# bee_duel_played.net
KiCad netlist of a schematic drawn in EAGLE
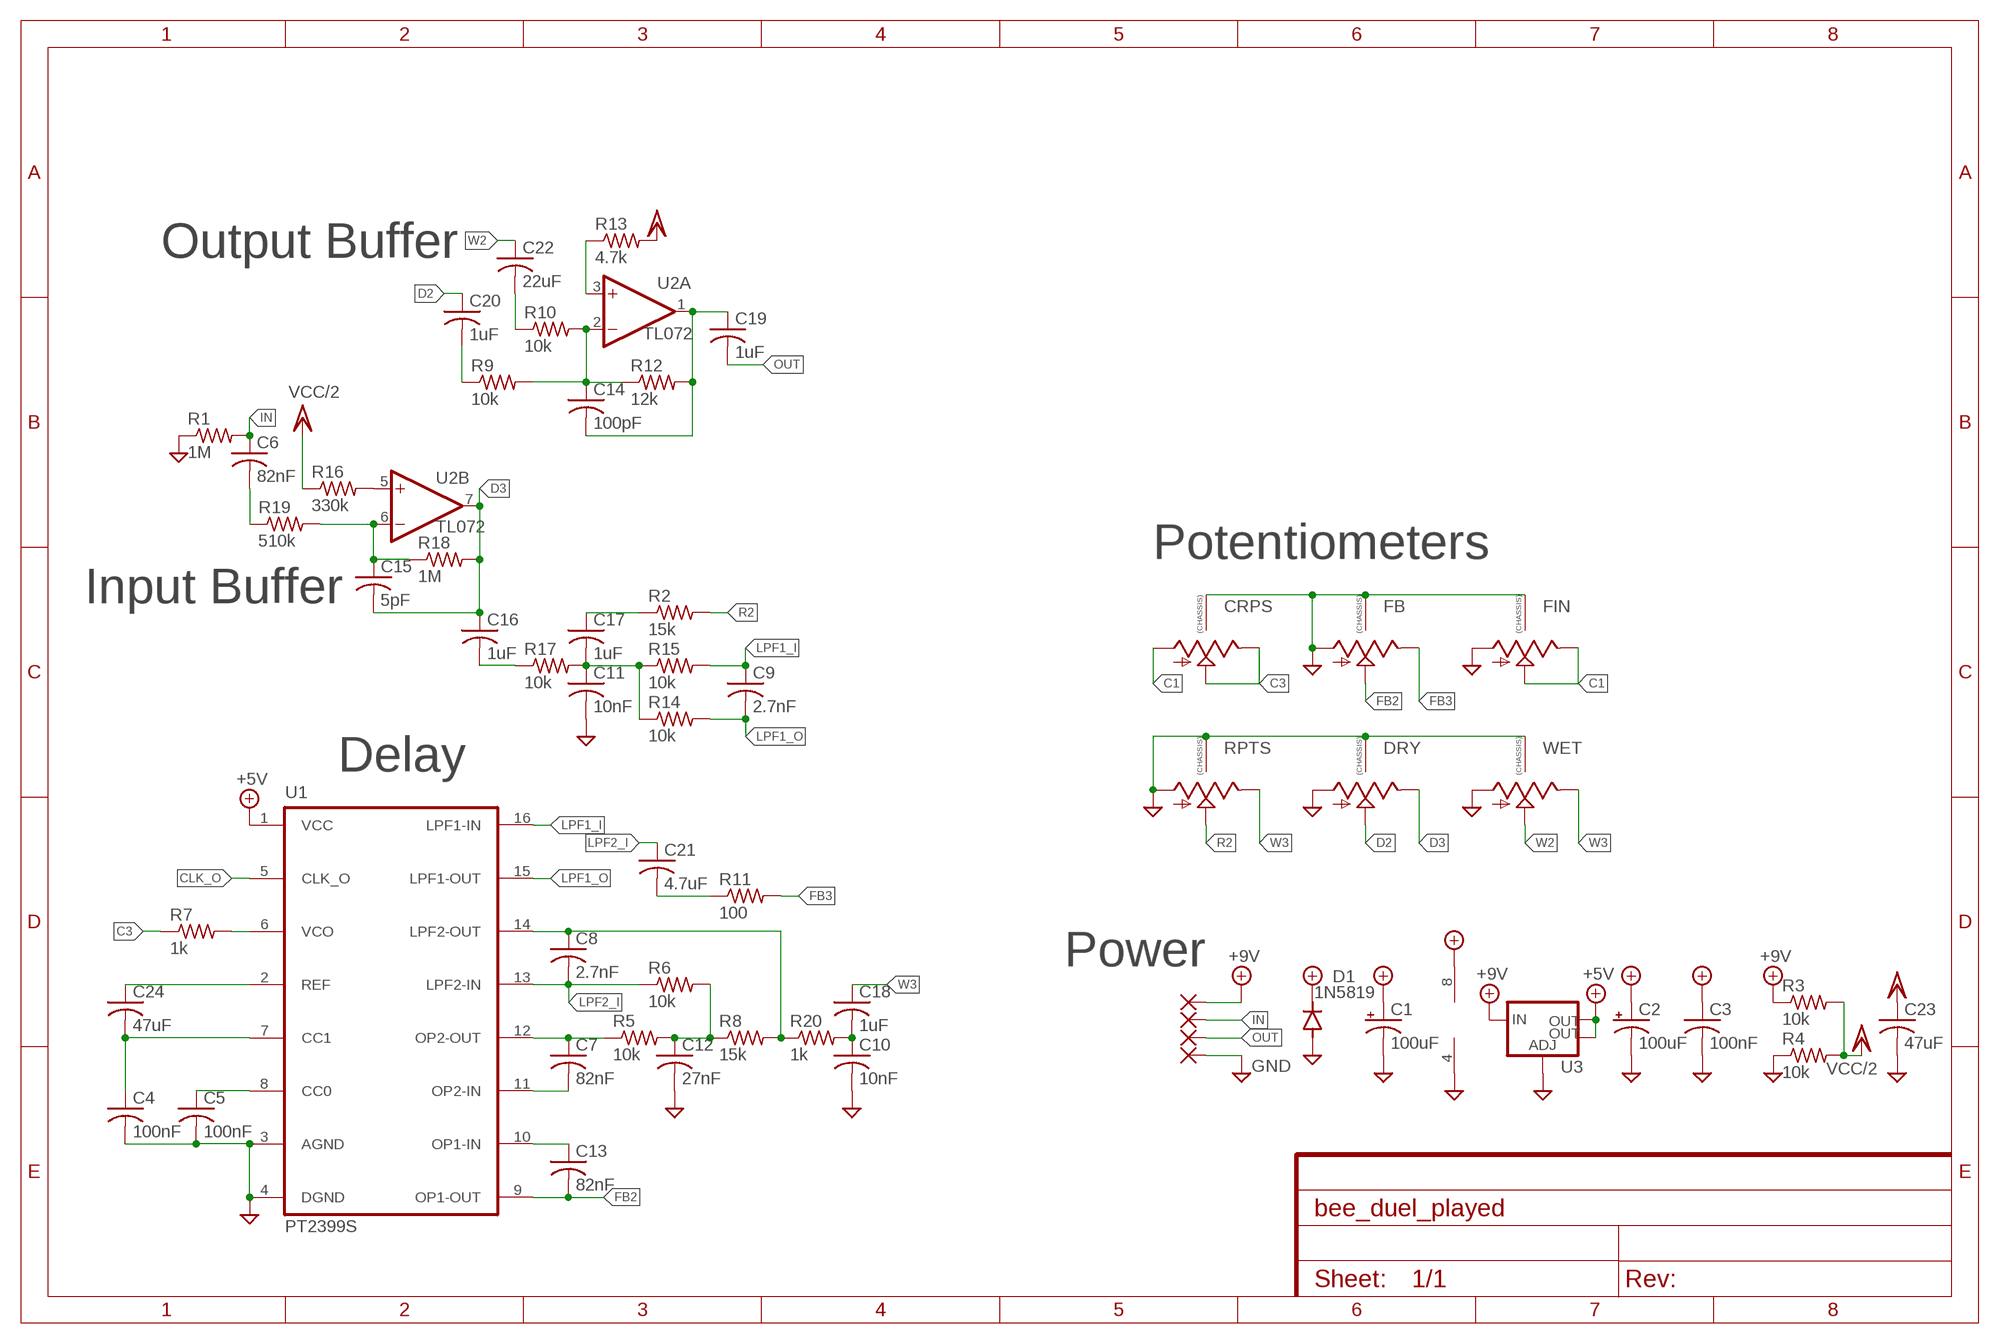
[diagram p0: schematic, sheet 1]

(export (version "E")
  (design (tool "Eeschema 10.0.6"))
  (components
    (comp (ref "C1")
      (value "100uF")
      (footprint "eagle-import:CPOL-RADIAL-2.5MM-6.5MM")
      (libsource (lib "eagle-import") (part "100UF-POLAR-RADIAL-2.5MM-25V-20%"))
    )
    (comp (ref "C2")
      (value "100uF")
      (footprint "eagle-import:CPOL-RADIAL-2.5MM-6.5MM")
      (libsource (lib "eagle-import") (part "100UF-POLAR-RADIAL-2.5MM-25V-20%"))
    )
    (comp (ref "C3")
      (value "100nF")
      (footprint "eagle-import:C0603")
      (libsource (lib "eagle-import") (part "C-USC0603"))
    )
    (comp (ref "C4")
      (value "100nF")
      (footprint "eagle-import:C0603")
      (libsource (lib "eagle-import") (part "C-USC0603"))
    )
    (comp (ref "C5")
      (value "100nF")
      (footprint "eagle-import:C0603")
      (libsource (lib "eagle-import") (part "C-USC0603"))
    )
    (comp (ref "C6")
      (value "82nF")
      (footprint "eagle-import:C0603")
      (libsource (lib "eagle-import") (part "C-USC0603"))
    )
    (comp (ref "C7")
      (value "82nF")
      (footprint "eagle-import:C0603")
      (libsource (lib "eagle-import") (part "C-USC0603"))
    )
    (comp (ref "C8")
      (value "2.7nF")
      (footprint "eagle-import:C0603")
      (libsource (lib "eagle-import") (part "C-USC0603"))
    )
    (comp (ref "C9")
      (value "2.7nF")
      (footprint "eagle-import:C0603")
      (libsource (lib "eagle-import") (part "C-USC0603"))
    )
    (comp (ref "C10")
      (value "10nF")
      (footprint "eagle-import:C0603")
      (libsource (lib "eagle-import") (part "C-USC0603"))
    )
    (comp (ref "C11")
      (value "10nF")
      (footprint "eagle-import:C0603")
      (libsource (lib "eagle-import") (part "C-USC0603"))
    )
    (comp (ref "C12")
      (value "27nF")
      (footprint "eagle-import:C0603")
      (libsource (lib "eagle-import") (part "C-USC0603"))
    )
    (comp (ref "C13")
      (value "82nF")
      (footprint "eagle-import:C0603")
      (libsource (lib "eagle-import") (part "C-USC0603"))
    )
    (comp (ref "C14")
      (value "100pF")
      (footprint "eagle-import:C0603")
      (libsource (lib "eagle-import") (part "C-USC0603"))
    )
    (comp (ref "C15")
      (value "5pF")
      (footprint "eagle-import:C0603")
      (libsource (lib "eagle-import") (part "C-USC0603"))
    )
    (comp (ref "C16")
      (value "1uF")
      (footprint "eagle-import:C0603")
      (libsource (lib "eagle-import") (part "C-USC0603"))
    )
    (comp (ref "C17")
      (value "1uF")
      (footprint "eagle-import:C0603")
      (libsource (lib "eagle-import") (part "C-USC0603"))
    )
    (comp (ref "C18")
      (value "1uF")
      (footprint "eagle-import:C0603")
      (libsource (lib "eagle-import") (part "C-USC0603"))
    )
    (comp (ref "C19")
      (value "1uF")
      (footprint "eagle-import:C0603")
      (libsource (lib "eagle-import") (part "C-USC0603"))
    )
    (comp (ref "C20")
      (value "1uF")
      (footprint "eagle-import:C0603")
      (libsource (lib "eagle-import") (part "C-USC0603"))
    )
    (comp (ref "C21")
      (value "4.7uF")
      (footprint "eagle-import:C0805")
      (libsource (lib "eagle-import") (part "C-USC0805"))
    )
    (comp (ref "C22")
      (value "22uF")
      (footprint "eagle-import:C1210")
      (libsource (lib "eagle-import") (part "adafruit_420_C-USC1210"))
    )
    (comp (ref "C23")
      (value "47uF")
      (footprint "eagle-import:C1210")
      (libsource (lib "eagle-import") (part "adafruit_420_C-USC1210"))
    )
    (comp (ref "C24")
      (value "47uF")
      (footprint "eagle-import:C1210")
      (libsource (lib "eagle-import") (part "adafruit_420_C-USC1210"))
    )
    (comp (ref "CRPS")
      (value "9MM_SNAP-IN_POT_CHASSIS")
      (footprint "eagle-import:9MM_SNAP-IN_POT")
      (libsource (lib "eagle-import") (part "9MM_SNAP-IN_POT_CHASSIS"))
    )
    (comp (ref "D1")
      (value "1N5819")
      (footprint "eagle-import:SOD123")
      (libsource (lib "eagle-import") (part "DIODE-SOD123"))
    )
    (comp (ref "DRY")
      (value "9MM_SNAP-IN_POT_CHASSIS")
      (footprint "eagle-import:9MM_SNAP-IN_POT")
      (libsource (lib "eagle-import") (part "9MM_SNAP-IN_POT_CHASSIS"))
    )
    (comp (ref "FB")
      (value "9MM_SNAP-IN_POT_CHASSIS")
      (footprint "eagle-import:9MM_SNAP-IN_POT")
      (libsource (lib "eagle-import") (part "9MM_SNAP-IN_POT_CHASSIS"))
    )
    (comp (ref "FIN")
      (value "9MM_SNAP-IN_POT_CHASSIS")
      (footprint "eagle-import:9MM_SNAP-IN_POT")
      (libsource (lib "eagle-import") (part "9MM_SNAP-IN_POT_CHASSIS"))
    )
    (comp (ref "PAD1")
      (value "1,6/0,8")
      (footprint "eagle-import:1,6_0,8")
      (libsource (lib "eagle-import") (part "1,6/0,8"))
    )
    (comp (ref "PAD2")
      (value "1,6/0,8")
      (footprint "eagle-import:1,6_0,8")
      (libsource (lib "eagle-import") (part "1,6/0,8"))
    )
    (comp (ref "PAD3")
      (value "1,6/0,8")
      (footprint "eagle-import:1,6_0,8")
      (libsource (lib "eagle-import") (part "1,6/0,8"))
    )
    (comp (ref "PAD4")
      (value "1,6/0,8")
      (footprint "eagle-import:1,6_0,8")
      (libsource (lib "eagle-import") (part "1,6/0,8"))
    )
    (comp (ref "R1")
      (value "1M")
      (footprint "eagle-import:R0603")
      (libsource (lib "eagle-import") (part "R-US_R0603"))
    )
    (comp (ref "R2")
      (value "15k")
      (footprint "eagle-import:R0603")
      (libsource (lib "eagle-import") (part "R-US_R0603"))
    )
    (comp (ref "R3")
      (value "10k")
      (footprint "eagle-import:R0603")
      (libsource (lib "eagle-import") (part "R-US_R0603"))
    )
    (comp (ref "R4")
      (value "10k")
      (footprint "eagle-import:R0603")
      (libsource (lib "eagle-import") (part "R-US_R0603"))
    )
    (comp (ref "R5")
      (value "10k")
      (footprint "eagle-import:R0603")
      (libsource (lib "eagle-import") (part "R-US_R0603"))
    )
    (comp (ref "R6")
      (value "10k")
      (footprint "eagle-import:R0603")
      (libsource (lib "eagle-import") (part "R-US_R0603"))
    )
    (comp (ref "R7")
      (value "1k")
      (footprint "eagle-import:R0603")
      (libsource (lib "eagle-import") (part "R-US_R0603"))
    )
    (comp (ref "R8")
      (value "15k")
      (footprint "eagle-import:R0603")
      (libsource (lib "eagle-import") (part "R-US_R0603"))
    )
    (comp (ref "R9")
      (value "10k")
      (footprint "eagle-import:R0603")
      (libsource (lib "eagle-import") (part "R-US_R0603"))
    )
    (comp (ref "R10")
      (value "10k")
      (footprint "eagle-import:R0603")
      (libsource (lib "eagle-import") (part "R-US_R0603"))
    )
    (comp (ref "R11")
      (value "100")
      (footprint "eagle-import:R0603")
      (libsource (lib "eagle-import") (part "R-US_R0603"))
    )
    (comp (ref "R12")
      (value "12k")
      (footprint "eagle-import:R0603")
      (libsource (lib "eagle-import") (part "R-US_R0603"))
    )
    (comp (ref "R13")
      (value "4.7k")
      (footprint "eagle-import:R0603")
      (libsource (lib "eagle-import") (part "R-US_R0603"))
    )
    (comp (ref "R14")
      (value "10k")
      (footprint "eagle-import:R0603")
      (libsource (lib "eagle-import") (part "R-US_R0603"))
    )
    (comp (ref "R15")
      (value "10k")
      (footprint "eagle-import:R0603")
      (libsource (lib "eagle-import") (part "R-US_R0603"))
    )
    (comp (ref "R16")
      (value "330k")
      (footprint "eagle-import:R0603")
      (libsource (lib "eagle-import") (part "R-US_R0603"))
    )
    (comp (ref "R17")
      (value "10k")
      (footprint "eagle-import:R0603")
      (libsource (lib "eagle-import") (part "R-US_R0603"))
    )
    (comp (ref "R18")
      (value "1M")
      (footprint "eagle-import:R0603")
      (libsource (lib "eagle-import") (part "R-US_R0603"))
    )
    (comp (ref "R19")
      (value "510k")
      (footprint "eagle-import:R0603")
      (libsource (lib "eagle-import") (part "R-US_R0603"))
    )
    (comp (ref "R20")
      (value "1k")
      (footprint "eagle-import:R0603")
      (libsource (lib "eagle-import") (part "R-US_R0603"))
    )
    (comp (ref "RPTS")
      (value "9MM_SNAP-IN_POT_CHASSIS")
      (footprint "eagle-import:9MM_SNAP-IN_POT")
      (libsource (lib "eagle-import") (part "9MM_SNAP-IN_POT_CHASSIS"))
    )
    (comp (ref "U1")
      (value "PT2399S")
      (footprint "eagle-import:SO16W")
      (libsource (lib "eagle-import") (part "PT2399S"))
    )
    (comp (ref "U2")
      (value "TL072")
      (footprint "eagle-import:TSSOP-8")
      (libsource (lib "eagle-import") (part "TL072TSSOP"))
    )
    (comp (ref "U3")
      (value "V_REG_LM1117SOT223")
      (footprint "eagle-import:SOT223")
      (libsource (lib "eagle-import") (part "V_REG_LM1117SOT223"))
    )
    (comp (ref "WET")
      (value "9MM_SNAP-IN_POT_CHASSIS")
      (footprint "eagle-import:9MM_SNAP-IN_POT")
      (libsource (lib "eagle-import") (part "9MM_SNAP-IN_POT_CHASSIS"))
    )
  )
  (nets
    (net (code "1") (name "+5V") (class "Default")
      (node (ref "C2") (pin "1") (pinfunction "+_1") (pintype "passive"))
      (node (ref "C3") (pin "1") (pinfunction "1_1") (pintype "passive"))
      (node (ref "U1") (pin "1") (pinfunction "VCC_1") (pintype "power_in"))
      (node (ref "U3") (pin "2") (pinfunction "OUT_2") (pintype "output"))
      (node (ref "U3") (pin "4") (pinfunction "OUT_4") (pintype "output"))
    )
    (net (code "2") (name "+9V") (class "Default")
      (node (ref "C1") (pin "1") (pinfunction "+_1") (pintype "passive"))
      (node (ref "D1") (pin "C") (pinfunction "C_C") (pintype "passive"))
      (node (ref "PAD1") (pin "1") (pinfunction "P_1") (pintype "passive"))
      (node (ref "R3") (pin "1") (pinfunction "1_1") (pintype "passive"))
      (node (ref "U2") (pin "8") (pinfunction "V+_8") (pintype "power_in"))
      (node (ref "U3") (pin "3") (pinfunction "IN_3") (pintype "input"))
    )
    (net (code "3") (name "C1") (class "Default")
      (node (ref "CRPS") (pin "1") (pinfunction "A_1") (pintype "passive"))
      (node (ref "FIN") (pin "2") (pinfunction "S_2") (pintype "passive"))
      (node (ref "FIN") (pin "3") (pinfunction "E_3") (pintype "passive"))
    )
    (net (code "4") (name "C3") (class "Default")
      (node (ref "CRPS") (pin "2") (pinfunction "S_2") (pintype "passive"))
      (node (ref "CRPS") (pin "3") (pinfunction "E_3") (pintype "passive"))
      (node (ref "R7") (pin "1") (pinfunction "1_1") (pintype "passive"))
    )
    (net (code "5") (name "CLK_O") (class "Default")
      (node (ref "U1") (pin "5") (pinfunction "CLK_O_5") (pintype "output"))
    )
    (net (code "6") (name "D2") (class "Default")
      (node (ref "C20") (pin "1") (pinfunction "1_1") (pintype "passive"))
      (node (ref "DRY") (pin "2") (pinfunction "S_2") (pintype "passive"))
    )
    (net (code "7") (name "D3") (class "Default")
      (node (ref "C15") (pin "2") (pinfunction "2_2") (pintype "passive"))
      (node (ref "C16") (pin "1") (pinfunction "1_1") (pintype "passive"))
      (node (ref "DRY") (pin "3") (pinfunction "E_3") (pintype "passive"))
      (node (ref "R18") (pin "2") (pinfunction "2_2") (pintype "passive"))
      (node (ref "U2") (pin "7") (pinfunction "OUT_7") (pintype "output"))
    )
    (net (code "8") (name "FB2") (class "Default")
      (node (ref "C13") (pin "2") (pinfunction "2_2") (pintype "passive"))
      (node (ref "FB") (pin "2") (pinfunction "S_2") (pintype "passive"))
      (node (ref "U1") (pin "9") (pinfunction "OP1-OUT_9") (pintype "output"))
    )
    (net (code "9") (name "FB3") (class "Default")
      (node (ref "FB") (pin "3") (pinfunction "E_3") (pintype "passive"))
      (node (ref "R11") (pin "2") (pinfunction "2_2") (pintype "passive"))
    )
    (net (code "10") (name "GND") (class "Default")
      (node (ref "C1") (pin "2") (pinfunction "-_2") (pintype "passive"))
      (node (ref "C10") (pin "2") (pinfunction "2_2") (pintype "passive"))
      (node (ref "C11") (pin "2") (pinfunction "2_2") (pintype "passive"))
      (node (ref "C12") (pin "2") (pinfunction "2_2") (pintype "passive"))
      (node (ref "C2") (pin "2") (pinfunction "-_2") (pintype "passive"))
      (node (ref "C23") (pin "2") (pinfunction "2_2") (pintype "passive"))
      (node (ref "C3") (pin "2") (pinfunction "2_2") (pintype "passive"))
      (node (ref "C4") (pin "2") (pinfunction "2_2") (pintype "passive"))
      (node (ref "C5") (pin "2") (pinfunction "2_2") (pintype "passive"))
      (node (ref "CRPS") (pin "CHASSIS1") (pinfunction "P$1_CHASSIS1") (pintype "passive"))
      (node (ref "CRPS") (pin "CHASSIS2") (pinfunction "P$1_CHASSIS2") (pintype "passive"))
      (node (ref "D1") (pin "A") (pinfunction "A_A") (pintype "passive"))
      (node (ref "DRY") (pin "1") (pinfunction "A_1") (pintype "passive"))
      (node (ref "DRY") (pin "CHASSIS1") (pinfunction "P$1_CHASSIS1") (pintype "passive"))
      (node (ref "DRY") (pin "CHASSIS2") (pinfunction "P$1_CHASSIS2") (pintype "passive"))
      (node (ref "FB") (pin "1") (pinfunction "A_1") (pintype "passive"))
      (node (ref "FB") (pin "CHASSIS1") (pinfunction "P$1_CHASSIS1") (pintype "passive"))
      (node (ref "FB") (pin "CHASSIS2") (pinfunction "P$1_CHASSIS2") (pintype "passive"))
      (node (ref "FIN") (pin "1") (pinfunction "A_1") (pintype "passive"))
      (node (ref "FIN") (pin "CHASSIS1") (pinfunction "P$1_CHASSIS1") (pintype "passive"))
      (node (ref "FIN") (pin "CHASSIS2") (pinfunction "P$1_CHASSIS2") (pintype "passive"))
      (node (ref "PAD4") (pin "1") (pinfunction "P_1") (pintype "passive"))
      (node (ref "R1") (pin "1") (pinfunction "1_1") (pintype "passive"))
      (node (ref "R4") (pin "1") (pinfunction "1_1") (pintype "passive"))
      (node (ref "RPTS") (pin "1") (pinfunction "A_1") (pintype "passive"))
      (node (ref "RPTS") (pin "CHASSIS1") (pinfunction "P$1_CHASSIS1") (pintype "passive"))
      (node (ref "RPTS") (pin "CHASSIS2") (pinfunction "P$1_CHASSIS2") (pintype "passive"))
      (node (ref "U1") (pin "3") (pinfunction "AGND_3") (pintype "power_in"))
      (node (ref "U1") (pin "4") (pinfunction "DGND_4") (pintype "power_in"))
      (node (ref "U2") (pin "4") (pinfunction "V-_4") (pintype "power_in"))
      (node (ref "U3") (pin "1") (pinfunction "ADJ_1") (pintype "input"))
      (node (ref "WET") (pin "1") (pinfunction "A_1") (pintype "passive"))
      (node (ref "WET") (pin "CHASSIS1") (pinfunction "P$1_CHASSIS1") (pintype "passive"))
      (node (ref "WET") (pin "CHASSIS2") (pinfunction "P$1_CHASSIS2") (pintype "passive"))
    )
    (net (code "11") (name "IN") (class "Default")
      (node (ref "C6") (pin "1") (pinfunction "1_1") (pintype "passive"))
      (node (ref "PAD2") (pin "1") (pinfunction "P_1") (pintype "passive"))
      (node (ref "R1") (pin "2") (pinfunction "2_2") (pintype "passive"))
    )
    (net (code "12") (name "LPF1_I") (class "Default")
      (node (ref "C9") (pin "1") (pinfunction "1_1") (pintype "passive"))
      (node (ref "R15") (pin "2") (pinfunction "2_2") (pintype "passive"))
      (node (ref "U1") (pin "16") (pinfunction "LPF1-IN_16") (pintype "input"))
    )
    (net (code "13") (name "LPF1_O") (class "Default")
      (node (ref "C9") (pin "2") (pinfunction "2_2") (pintype "passive"))
      (node (ref "R14") (pin "2") (pinfunction "2_2") (pintype "passive"))
      (node (ref "U1") (pin "15") (pinfunction "LPF1-OUT_15") (pintype "output"))
    )
    (net (code "14") (name "LPF2_I") (class "Default")
      (node (ref "C21") (pin "1") (pinfunction "1_1") (pintype "passive"))
      (node (ref "C8") (pin "2") (pinfunction "2_2") (pintype "passive"))
      (node (ref "R6") (pin "1") (pinfunction "1_1") (pintype "passive"))
      (node (ref "U1") (pin "13") (pinfunction "LPF2-IN_13") (pintype "input"))
    )
    (net (code "15") (name "Net-(C6-Pad2)") (class "Default")
      (node (ref "C6") (pin "2") (pinfunction "2_2") (pintype "passive"))
      (node (ref "R19") (pin "1") (pinfunction "1_1") (pintype "passive"))
    )
    (net (code "16") (name "Net-(C10-Pad1)") (class "Default")
      (node (ref "C10") (pin "1") (pinfunction "1_1") (pintype "passive"))
      (node (ref "C18") (pin "2") (pinfunction "2_2") (pintype "passive"))
      (node (ref "R20") (pin "2") (pinfunction "2_2") (pintype "passive"))
    )
    (net (code "17") (name "Net-(C11-Pad1)") (class "Default")
      (node (ref "C11") (pin "1") (pinfunction "1_1") (pintype "passive"))
      (node (ref "C17") (pin "2") (pinfunction "2_2") (pintype "passive"))
      (node (ref "R14") (pin "1") (pinfunction "1_1") (pintype "passive"))
      (node (ref "R15") (pin "1") (pinfunction "1_1") (pintype "passive"))
      (node (ref "R17") (pin "2") (pinfunction "2_2") (pintype "passive"))
    )
    (net (code "18") (name "Net-(C12-Pad1)") (class "Default")
      (node (ref "C12") (pin "1") (pinfunction "1_1") (pintype "passive"))
      (node (ref "R5") (pin "2") (pinfunction "2_2") (pintype "passive"))
      (node (ref "R6") (pin "2") (pinfunction "2_2") (pintype "passive"))
      (node (ref "R8") (pin "1") (pinfunction "1_1") (pintype "passive"))
    )
    (net (code "19") (name "Net-(C16-Pad2)") (class "Default")
      (node (ref "C16") (pin "2") (pinfunction "2_2") (pintype "passive"))
      (node (ref "R17") (pin "1") (pinfunction "1_1") (pintype "passive"))
    )
    (net (code "20") (name "Net-(C17-Pad1)") (class "Default")
      (node (ref "C17") (pin "1") (pinfunction "1_1") (pintype "passive"))
      (node (ref "R2") (pin "1") (pinfunction "1_1") (pintype "passive"))
    )
    (net (code "21") (name "Net-(C20-Pad2)") (class "Default")
      (node (ref "C20") (pin "2") (pinfunction "2_2") (pintype "passive"))
      (node (ref "R9") (pin "1") (pinfunction "1_1") (pintype "passive"))
    )
    (net (code "22") (name "Net-(C21-Pad2)") (class "Default")
      (node (ref "C21") (pin "2") (pinfunction "2_2") (pintype "passive"))
      (node (ref "R11") (pin "1") (pinfunction "1_1") (pintype "passive"))
    )
    (net (code "23") (name "Net-(C22-Pad2)") (class "Default")
      (node (ref "C22") (pin "2") (pinfunction "2_2") (pintype "passive"))
      (node (ref "R10") (pin "1") (pinfunction "1_1") (pintype "passive"))
    )
    (net (code "24") (name "Net-(U1-CC0)") (class "Default")
      (node (ref "C5") (pin "1") (pinfunction "1_1") (pintype "passive"))
      (node (ref "U1") (pin "8") (pinfunction "CC0_8") (pintype "input"))
    )
    (net (code "25") (name "Net-(U1-CC1)") (class "Default")
      (node (ref "C24") (pin "2") (pinfunction "2_2") (pintype "passive"))
      (node (ref "C4") (pin "1") (pinfunction "1_1") (pintype "passive"))
      (node (ref "U1") (pin "7") (pinfunction "CC1_7") (pintype "input"))
    )
    (net (code "26") (name "Net-(U1-LPF2-OUT)") (class "Default")
      (node (ref "C8") (pin "1") (pinfunction "1_1") (pintype "passive"))
      (node (ref "R20") (pin "1") (pinfunction "1_1") (pintype "passive"))
      (node (ref "R8") (pin "2") (pinfunction "2_2") (pintype "passive"))
      (node (ref "U1") (pin "14") (pinfunction "LPF2-OUT_14") (pintype "output"))
    )
    (net (code "27") (name "Net-(U1-OP1-IN)") (class "Default")
      (node (ref "C13") (pin "1") (pinfunction "1_1") (pintype "passive"))
      (node (ref "U1") (pin "10") (pinfunction "OP1-IN_10") (pintype "input"))
    )
    (net (code "28") (name "Net-(U1-OP2-IN)") (class "Default")
      (node (ref "C7") (pin "2") (pinfunction "2_2") (pintype "passive"))
      (node (ref "U1") (pin "11") (pinfunction "OP2-IN_11") (pintype "input"))
    )
    (net (code "29") (name "Net-(U1-OP2-OUT)") (class "Default")
      (node (ref "C7") (pin "1") (pinfunction "1_1") (pintype "passive"))
      (node (ref "R5") (pin "1") (pinfunction "1_1") (pintype "passive"))
      (node (ref "U1") (pin "12") (pinfunction "OP2-OUT_12") (pintype "output"))
    )
    (net (code "30") (name "Net-(U1-REF)") (class "Default")
      (node (ref "C24") (pin "1") (pinfunction "1_1") (pintype "passive"))
      (node (ref "U1") (pin "2") (pinfunction "REF_2") (pintype "input"))
    )
    (net (code "31") (name "Net-(U1-VCO)") (class "Default")
      (node (ref "R7") (pin "2") (pinfunction "2_2") (pintype "passive"))
      (node (ref "U1") (pin "6") (pinfunction "VCO_6") (pintype "input"))
    )
    (net (code "32") (name "Net-(U2A-+IN)") (class "Default")
      (node (ref "R13") (pin "1") (pinfunction "1_1") (pintype "passive"))
      (node (ref "U2") (pin "3") (pinfunction "+IN_3") (pintype "input"))
    )
    (net (code "33") (name "Net-(U2A--IN)") (class "Default")
      (node (ref "C14") (pin "1") (pinfunction "1_1") (pintype "passive"))
      (node (ref "R10") (pin "2") (pinfunction "2_2") (pintype "passive"))
      (node (ref "R12") (pin "1") (pinfunction "1_1") (pintype "passive"))
      (node (ref "R9") (pin "2") (pinfunction "2_2") (pintype "passive"))
      (node (ref "U2") (pin "2") (pinfunction "-IN_2") (pintype "input"))
    )
    (net (code "34") (name "Net-(U2A-OUT)") (class "Default")
      (node (ref "C14") (pin "2") (pinfunction "2_2") (pintype "passive"))
      (node (ref "C19") (pin "1") (pinfunction "1_1") (pintype "passive"))
      (node (ref "R12") (pin "2") (pinfunction "2_2") (pintype "passive"))
      (node (ref "U2") (pin "1") (pinfunction "OUT_1") (pintype "output"))
    )
    (net (code "35") (name "Net-(U2B-+IN)") (class "Default")
      (node (ref "R16") (pin "2") (pinfunction "2_2") (pintype "passive"))
      (node (ref "U2") (pin "5") (pinfunction "+IN_5") (pintype "input"))
    )
    (net (code "36") (name "Net-(U2B--IN)") (class "Default")
      (node (ref "C15") (pin "1") (pinfunction "1_1") (pintype "passive"))
      (node (ref "R18") (pin "1") (pinfunction "1_1") (pintype "passive"))
      (node (ref "R19") (pin "2") (pinfunction "2_2") (pintype "passive"))
      (node (ref "U2") (pin "6") (pinfunction "-IN_6") (pintype "input"))
    )
    (net (code "37") (name "OUT") (class "Default")
      (node (ref "C19") (pin "2") (pinfunction "2_2") (pintype "passive"))
      (node (ref "PAD3") (pin "1") (pinfunction "P_1") (pintype "passive"))
    )
    (net (code "38") (name "R2") (class "Default")
      (node (ref "R2") (pin "2") (pinfunction "2_2") (pintype "passive"))
      (node (ref "RPTS") (pin "2") (pinfunction "S_2") (pintype "passive"))
    )
    (net (code "39") (name "VCC{slash}2") (class "Default")
      (node (ref "C23") (pin "1") (pinfunction "1_1") (pintype "passive"))
      (node (ref "R13") (pin "2") (pinfunction "2_2") (pintype "passive"))
      (node (ref "R16") (pin "1") (pinfunction "1_1") (pintype "passive"))
      (node (ref "R3") (pin "2") (pinfunction "2_2") (pintype "passive"))
      (node (ref "R4") (pin "2") (pinfunction "2_2") (pintype "passive"))
    )
    (net (code "40") (name "W2") (class "Default")
      (node (ref "C22") (pin "1") (pinfunction "1_1") (pintype "passive"))
      (node (ref "WET") (pin "2") (pinfunction "S_2") (pintype "passive"))
    )
    (net (code "41") (name "W3") (class "Default")
      (node (ref "C18") (pin "1") (pinfunction "1_1") (pintype "passive"))
      (node (ref "RPTS") (pin "3") (pinfunction "E_3") (pintype "passive"))
      (node (ref "WET") (pin "3") (pinfunction "E_3") (pintype "passive"))
    )
  )
)
